# IR.net
KiCad netlist of a schematic drawn in EAGLE
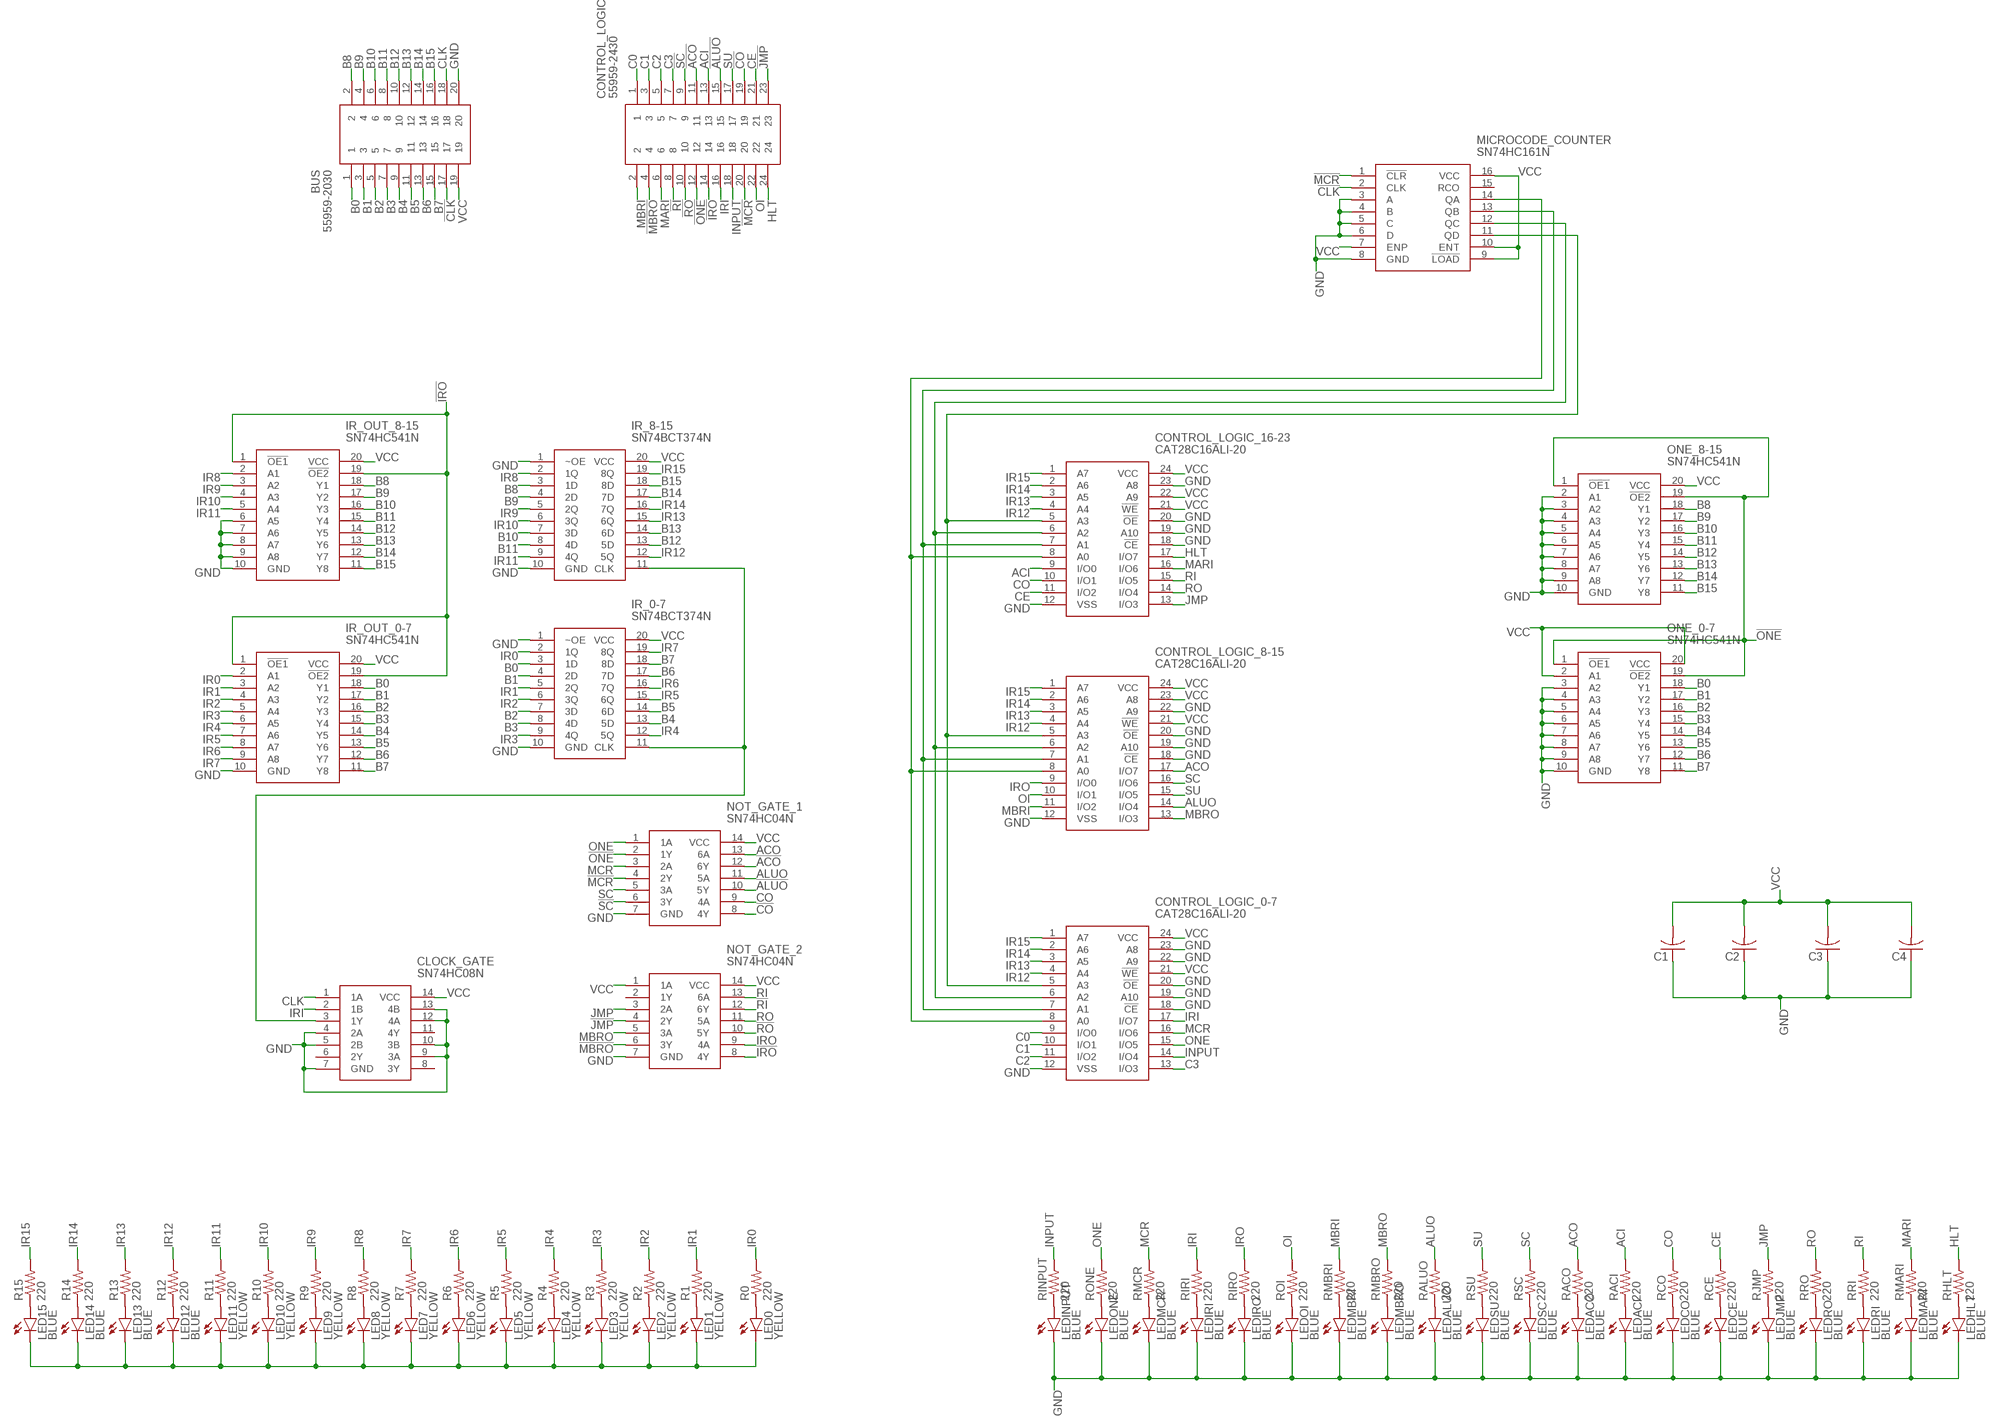
[diagram p0: schematic, sheet 1]

(export (version "E")
  (design (tool "Eeschema 10.0.6"))
  (components
    (comp (ref "BUS")
      (value "55959-2030")
      (footprint "eagle-import:55959-2030_1")
      (fields (field (name "MOUSER_PART_NUMBER") "538-55959-2030"))
      (libsource (lib "eagle-import") (part "55959-2030"))
    )
    (comp (ref "C1")
      (value "C-US025-024X044")
      (footprint "eagle-import:C025-024X044")
      (libsource (lib "eagle-import") (part "C-US025-024X044"))
    )
    (comp (ref "C2")
      (value "C-US025-024X044")
      (footprint "eagle-import:C025-024X044")
      (libsource (lib "eagle-import") (part "C-US025-024X044"))
    )
    (comp (ref "C3")
      (value "C-US025-024X044")
      (footprint "eagle-import:C025-024X044")
      (libsource (lib "eagle-import") (part "C-US025-024X044"))
    )
    (comp (ref "C4")
      (value "C-US025-024X044")
      (footprint "eagle-import:C025-024X044")
      (libsource (lib "eagle-import") (part "C-US025-024X044"))
    )
    (comp (ref "CLOCK_GATE")
      (value "SN74HC08N")
      (footprint "eagle-import:DIP794W53P254L1930H508Q14N")
      (fields (field (name "MOUSER_PART_NUMBER") "595-SN74HC08N"))
      (libsource (lib "eagle-import") (part "SN74HC08N"))
    )
    (comp (ref "CONTROL_LOGIC")
      (value "55959-2430")
      (footprint "eagle-import:559592430")
      (fields (field (name "MOUSER_PART_NUMBER") "538-55959-2430"))
      (libsource (lib "eagle-import") (part "55959-2430"))
    )
    (comp (ref "CONTROL_LOGIC_0-7")
      (value "CAT28C16ALI-20")
      (footprint "eagle-import:DIP1651W55P254L3188H635Q24N")
      (libsource (lib "eagle-import") (part "CAT28C16ALI-20"))
    )
    (comp (ref "CONTROL_LOGIC_8-15")
      (value "CAT28C16ALI-20")
      (footprint "eagle-import:DIP1651W55P254L3188H635Q24N")
      (libsource (lib "eagle-import") (part "CAT28C16ALI-20"))
    )
    (comp (ref "CONTROL_LOGIC_16-23")
      (value "CAT28C16ALI-20")
      (footprint "eagle-import:DIP1651W55P254L3188H635Q24N")
      (libsource (lib "eagle-import") (part "CAT28C16ALI-20"))
    )
    (comp (ref "IR_0-7")
      (value "SN74BCT374N")
      (footprint "eagle-import:DIP254P762X508-20")
      (fields (field (name "MOUSER_PART_NUMBER") "595-SN74BCT374N"))
      (libsource (lib "eagle-import") (part "SN74BCT374N"))
    )
    (comp (ref "IR_8-15")
      (value "SN74BCT374N")
      (footprint "eagle-import:DIP254P762X508-20")
      (fields (field (name "MOUSER_PART_NUMBER") "595-SN74BCT374N"))
      (libsource (lib "eagle-import") (part "SN74BCT374N"))
    )
    (comp (ref "IR_OUT_0-7")
      (value "SN74HC541N")
      (footprint "eagle-import:DIP794W53P254L2540H508Q20N")
      (fields (field (name "MOUSER_PART_NUMBER") "595-SN74HC541N"))
      (libsource (lib "eagle-import") (part "SN74HC541N"))
    )
    (comp (ref "IR_OUT_8-15")
      (value "SN74HC541N")
      (footprint "eagle-import:DIP794W53P254L2540H508Q20N")
      (fields (field (name "MOUSER_PART_NUMBER") "595-SN74HC541N"))
      (libsource (lib "eagle-import") (part "SN74HC541N"))
    )
    (comp (ref "LED0")
      (value "YELLOW")
      (footprint "eagle-import:LED3MM")
      (libsource (lib "eagle-import") (part "LED3MM"))
    )
    (comp (ref "LED1")
      (value "YELLOW")
      (footprint "eagle-import:LED3MM")
      (libsource (lib "eagle-import") (part "LED3MM"))
    )
    (comp (ref "LED2")
      (value "YELLOW")
      (footprint "eagle-import:LED3MM")
      (libsource (lib "eagle-import") (part "LED3MM"))
    )
    (comp (ref "LED3")
      (value "YELLOW")
      (footprint "eagle-import:LED3MM")
      (libsource (lib "eagle-import") (part "LED3MM"))
    )
    (comp (ref "LED4")
      (value "YELLOW")
      (footprint "eagle-import:LED3MM")
      (libsource (lib "eagle-import") (part "LED3MM"))
    )
    (comp (ref "LED5")
      (value "YELLOW")
      (footprint "eagle-import:LED3MM")
      (libsource (lib "eagle-import") (part "LED3MM"))
    )
    (comp (ref "LED6")
      (value "YELLOW")
      (footprint "eagle-import:LED3MM")
      (libsource (lib "eagle-import") (part "LED3MM"))
    )
    (comp (ref "LED7")
      (value "YELLOW")
      (footprint "eagle-import:LED3MM")
      (libsource (lib "eagle-import") (part "LED3MM"))
    )
    (comp (ref "LED8")
      (value "YELLOW")
      (footprint "eagle-import:LED3MM")
      (libsource (lib "eagle-import") (part "LED3MM"))
    )
    (comp (ref "LED9")
      (value "YELLOW")
      (footprint "eagle-import:LED3MM")
      (libsource (lib "eagle-import") (part "LED3MM"))
    )
    (comp (ref "LED10")
      (value "YELLOW")
      (footprint "eagle-import:LED3MM")
      (libsource (lib "eagle-import") (part "LED3MM"))
    )
    (comp (ref "LED11")
      (value "YELLOW")
      (footprint "eagle-import:LED3MM")
      (libsource (lib "eagle-import") (part "LED3MM"))
    )
    (comp (ref "LED12")
      (value "BLUE")
      (footprint "eagle-import:LED3MM")
      (libsource (lib "eagle-import") (part "LED3MM"))
    )
    (comp (ref "LED13")
      (value "BLUE")
      (footprint "eagle-import:LED3MM")
      (libsource (lib "eagle-import") (part "LED3MM"))
    )
    (comp (ref "LED14")
      (value "BLUE")
      (footprint "eagle-import:LED3MM")
      (libsource (lib "eagle-import") (part "LED3MM"))
    )
    (comp (ref "LED15")
      (value "BLUE")
      (footprint "eagle-import:LED3MM")
      (libsource (lib "eagle-import") (part "LED3MM"))
    )
    (comp (ref "LEDACI")
      (value "BLUE")
      (footprint "eagle-import:LED3MM")
      (libsource (lib "eagle-import") (part "LED3MM"))
    )
    (comp (ref "LEDACO")
      (value "BLUE")
      (footprint "eagle-import:LED3MM")
      (libsource (lib "eagle-import") (part "LED3MM"))
    )
    (comp (ref "LEDALUO")
      (value "BLUE")
      (footprint "eagle-import:LED3MM")
      (libsource (lib "eagle-import") (part "LED3MM"))
    )
    (comp (ref "LEDCE")
      (value "BLUE")
      (footprint "eagle-import:LED3MM")
      (libsource (lib "eagle-import") (part "LED3MM"))
    )
    (comp (ref "LEDCO")
      (value "BLUE")
      (footprint "eagle-import:LED3MM")
      (libsource (lib "eagle-import") (part "LED3MM"))
    )
    (comp (ref "LEDHLT")
      (value "BLUE")
      (footprint "eagle-import:LED3MM")
      (libsource (lib "eagle-import") (part "LED3MM"))
    )
    (comp (ref "LEDINPUT")
      (value "BLUE")
      (footprint "eagle-import:LED3MM")
      (libsource (lib "eagle-import") (part "LED3MM"))
    )
    (comp (ref "LEDIRI")
      (value "BLUE")
      (footprint "eagle-import:LED3MM")
      (libsource (lib "eagle-import") (part "LED3MM"))
    )
    (comp (ref "LEDIRO")
      (value "BLUE")
      (footprint "eagle-import:LED3MM")
      (libsource (lib "eagle-import") (part "LED3MM"))
    )
    (comp (ref "LEDJMP")
      (value "BLUE")
      (footprint "eagle-import:LED3MM")
      (libsource (lib "eagle-import") (part "LED3MM"))
    )
    (comp (ref "LEDMARI")
      (value "BLUE")
      (footprint "eagle-import:LED3MM")
      (libsource (lib "eagle-import") (part "LED3MM"))
    )
    (comp (ref "LEDMBRI")
      (value "BLUE")
      (footprint "eagle-import:LED3MM")
      (libsource (lib "eagle-import") (part "LED3MM"))
    )
    (comp (ref "LEDMBRO")
      (value "BLUE")
      (footprint "eagle-import:LED3MM")
      (libsource (lib "eagle-import") (part "LED3MM"))
    )
    (comp (ref "LEDMCR")
      (value "BLUE")
      (footprint "eagle-import:LED3MM")
      (libsource (lib "eagle-import") (part "LED3MM"))
    )
    (comp (ref "LEDOI")
      (value "BLUE")
      (footprint "eagle-import:LED3MM")
      (libsource (lib "eagle-import") (part "LED3MM"))
    )
    (comp (ref "LEDONE")
      (value "BLUE")
      (footprint "eagle-import:LED3MM")
      (libsource (lib "eagle-import") (part "LED3MM"))
    )
    (comp (ref "LEDRI")
      (value "BLUE")
      (footprint "eagle-import:LED3MM")
      (libsource (lib "eagle-import") (part "LED3MM"))
    )
    (comp (ref "LEDRO")
      (value "BLUE")
      (footprint "eagle-import:LED3MM")
      (libsource (lib "eagle-import") (part "LED3MM"))
    )
    (comp (ref "LEDSC")
      (value "BLUE")
      (footprint "eagle-import:LED3MM")
      (libsource (lib "eagle-import") (part "LED3MM"))
    )
    (comp (ref "LEDSU")
      (value "BLUE")
      (footprint "eagle-import:LED3MM")
      (libsource (lib "eagle-import") (part "LED3MM"))
    )
    (comp (ref "MICROCODE_COUNTER")
      (value "SN74HC161N")
      (footprint "eagle-import:DIP794W53P254L1930H508Q16N")
      (fields (field (name "MOUSER_PART_NUMBER") "595-SN74HC161N"))
      (libsource (lib "eagle-import") (part "SN74HC161N"))
    )
    (comp (ref "NOT_GATE_1")
      (value "SN74HC04N")
      (footprint "eagle-import:DIP794W53P254L1930H508Q14N")
      (fields (field (name "MOUSER_PART_NUMBER") "595-SN74HC04N"))
      (libsource (lib "eagle-import") (part "SN74HC04N"))
    )
    (comp (ref "NOT_GATE_2")
      (value "SN74HC04N")
      (footprint "eagle-import:DIP794W53P254L1930H508Q14N")
      (fields (field (name "MOUSER_PART_NUMBER") "595-SN74HC04N"))
      (libsource (lib "eagle-import") (part "SN74HC04N"))
    )
    (comp (ref "ONE_0-7")
      (value "SN74HC541N")
      (footprint "eagle-import:DIP794W53P254L2540H508Q20N")
      (fields (field (name "MOUSER_PART_NUMBER") "595-SN74HC541N"))
      (libsource (lib "eagle-import") (part "SN74HC541N"))
    )
    (comp (ref "ONE_8-15")
      (value "SN74HC541N")
      (footprint "eagle-import:DIP794W53P254L2540H508Q20N")
      (fields (field (name "MOUSER_PART_NUMBER") "595-SN74HC541N"))
      (libsource (lib "eagle-import") (part "SN74HC541N"))
    )
    (comp (ref "R0")
      (value "220")
      (footprint "eagle-import:0204_7")
      (libsource (lib "eagle-import") (part "R-US_0204/7"))
    )
    (comp (ref "R1")
      (value "220")
      (footprint "eagle-import:0204_7")
      (libsource (lib "eagle-import") (part "R-US_0204/7"))
    )
    (comp (ref "R2")
      (value "220")
      (footprint "eagle-import:0204_7")
      (libsource (lib "eagle-import") (part "R-US_0204/7"))
    )
    (comp (ref "R3")
      (value "220")
      (footprint "eagle-import:0204_7")
      (libsource (lib "eagle-import") (part "R-US_0204/7"))
    )
    (comp (ref "R4")
      (value "220")
      (footprint "eagle-import:0204_7")
      (libsource (lib "eagle-import") (part "R-US_0204/7"))
    )
    (comp (ref "R5")
      (value "220")
      (footprint "eagle-import:0204_7")
      (libsource (lib "eagle-import") (part "R-US_0204/7"))
    )
    (comp (ref "R6")
      (value "220")
      (footprint "eagle-import:0204_7")
      (libsource (lib "eagle-import") (part "R-US_0204/7"))
    )
    (comp (ref "R7")
      (value "220")
      (footprint "eagle-import:0204_7")
      (libsource (lib "eagle-import") (part "R-US_0204/7"))
    )
    (comp (ref "R8")
      (value "220")
      (footprint "eagle-import:0204_7")
      (libsource (lib "eagle-import") (part "R-US_0204/7"))
    )
    (comp (ref "R9")
      (value "220")
      (footprint "eagle-import:0204_7")
      (libsource (lib "eagle-import") (part "R-US_0204/7"))
    )
    (comp (ref "R10")
      (value "220")
      (footprint "eagle-import:0204_7")
      (libsource (lib "eagle-import") (part "R-US_0204/7"))
    )
    (comp (ref "R11")
      (value "220")
      (footprint "eagle-import:0204_7")
      (libsource (lib "eagle-import") (part "R-US_0204/7"))
    )
    (comp (ref "R12")
      (value "220")
      (footprint "eagle-import:0204_7")
      (libsource (lib "eagle-import") (part "R-US_0204/7"))
    )
    (comp (ref "R13")
      (value "220")
      (footprint "eagle-import:0204_7")
      (libsource (lib "eagle-import") (part "R-US_0204/7"))
    )
    (comp (ref "R14")
      (value "220")
      (footprint "eagle-import:0204_7")
      (libsource (lib "eagle-import") (part "R-US_0204/7"))
    )
    (comp (ref "R15")
      (value "220")
      (footprint "eagle-import:0204_7")
      (libsource (lib "eagle-import") (part "R-US_0204/7"))
    )
    (comp (ref "RACI")
      (value "220")
      (footprint "eagle-import:0204_7")
      (libsource (lib "eagle-import") (part "R-US_0204/7"))
    )
    (comp (ref "RACO")
      (value "220")
      (footprint "eagle-import:0204_7")
      (libsource (lib "eagle-import") (part "R-US_0204/7"))
    )
    (comp (ref "RALUO")
      (value "220")
      (footprint "eagle-import:0204_7")
      (libsource (lib "eagle-import") (part "R-US_0204/7"))
    )
    (comp (ref "RCE")
      (value "220")
      (footprint "eagle-import:0204_7")
      (libsource (lib "eagle-import") (part "R-US_0204/7"))
    )
    (comp (ref "RCO")
      (value "220")
      (footprint "eagle-import:0204_7")
      (libsource (lib "eagle-import") (part "R-US_0204/7"))
    )
    (comp (ref "RHLT")
      (value "220")
      (footprint "eagle-import:0204_7")
      (libsource (lib "eagle-import") (part "R-US_0204/7"))
    )
    (comp (ref "RINPUT")
      (value "220")
      (footprint "eagle-import:0204_7")
      (libsource (lib "eagle-import") (part "R-US_0204/7"))
    )
    (comp (ref "RIRI")
      (value "220")
      (footprint "eagle-import:0204_7")
      (libsource (lib "eagle-import") (part "R-US_0204/7"))
    )
    (comp (ref "RIRO")
      (value "220")
      (footprint "eagle-import:0204_7")
      (libsource (lib "eagle-import") (part "R-US_0204/7"))
    )
    (comp (ref "RJMP")
      (value "220")
      (footprint "eagle-import:0204_7")
      (libsource (lib "eagle-import") (part "R-US_0204/7"))
    )
    (comp (ref "RMARI")
      (value "220")
      (footprint "eagle-import:0204_7")
      (libsource (lib "eagle-import") (part "R-US_0204/7"))
    )
    (comp (ref "RMBRI")
      (value "220")
      (footprint "eagle-import:0204_7")
      (libsource (lib "eagle-import") (part "R-US_0204/7"))
    )
    (comp (ref "RMBRO")
      (value "220")
      (footprint "eagle-import:0204_7")
      (libsource (lib "eagle-import") (part "R-US_0204/7"))
    )
    (comp (ref "RMCR")
      (value "220")
      (footprint "eagle-import:0204_7")
      (libsource (lib "eagle-import") (part "R-US_0204/7"))
    )
    (comp (ref "ROI")
      (value "220")
      (footprint "eagle-import:0204_7")
      (libsource (lib "eagle-import") (part "R-US_0204/7"))
    )
    (comp (ref "RONE")
      (value "220")
      (footprint "eagle-import:0204_7")
      (libsource (lib "eagle-import") (part "R-US_0204/7"))
    )
    (comp (ref "RRI")
      (value "220")
      (footprint "eagle-import:0204_7")
      (libsource (lib "eagle-import") (part "R-US_0204/7"))
    )
    (comp (ref "RRO")
      (value "220")
      (footprint "eagle-import:0204_7")
      (libsource (lib "eagle-import") (part "R-US_0204/7"))
    )
    (comp (ref "RSC")
      (value "220")
      (footprint "eagle-import:0204_7")
      (libsource (lib "eagle-import") (part "R-US_0204/7"))
    )
    (comp (ref "RSU")
      (value "220")
      (footprint "eagle-import:0204_7")
      (libsource (lib "eagle-import") (part "R-US_0204/7"))
    )
  )
  (nets
    (net (code "1") (name "/ACI") (class "Default")
      (node (ref "CONTROL_LOGIC") (pin "13") (pinfunction "13_13") (pintype "bidirectional"))
      (node (ref "CONTROL_LOGIC_16-23") (pin "9") (pinfunction "I/O0_9") (pintype "bidirectional"))
      (node (ref "RACI") (pin "2") (pinfunction "2_2") (pintype "passive"))
    )
    (net (code "2") (name "/ACO") (class "Default")
      (node (ref "CONTROL_LOGIC_8-15") (pin "17") (pinfunction "I/O7_17") (pintype "bidirectional"))
      (node (ref "NOT_GATE_1") (pin "13") (pinfunction "6A_13") (pintype "bidirectional"))
      (node (ref "RACO") (pin "2") (pinfunction "2_2") (pintype "passive"))
    )
    (net (code "3") (name "/ALUO") (class "Default")
      (node (ref "CONTROL_LOGIC_8-15") (pin "14") (pinfunction "I/O4_14") (pintype "bidirectional"))
      (node (ref "NOT_GATE_1") (pin "11") (pinfunction "5A_11") (pintype "bidirectional"))
      (node (ref "RALUO") (pin "2") (pinfunction "2_2") (pintype "passive"))
    )
    (net (code "4") (name "/B0") (class "Default")
      (node (ref "BUS") (pin "1") (pinfunction "1_1") (pintype "bidirectional"))
      (node (ref "IR_0-7") (pin "3") (pinfunction "1D_3") (pintype "bidirectional"))
      (node (ref "IR_OUT_0-7") (pin "18") (pinfunction "Y1_18") (pintype "bidirectional"))
      (node (ref "ONE_0-7") (pin "18") (pinfunction "Y1_18") (pintype "bidirectional"))
    )
    (net (code "5") (name "/B1") (class "Default")
      (node (ref "BUS") (pin "3") (pinfunction "3_3") (pintype "bidirectional"))
      (node (ref "IR_0-7") (pin "4") (pinfunction "2D_4") (pintype "bidirectional"))
      (node (ref "IR_OUT_0-7") (pin "17") (pinfunction "Y2_17") (pintype "bidirectional"))
      (node (ref "ONE_0-7") (pin "17") (pinfunction "Y2_17") (pintype "bidirectional"))
    )
    (net (code "6") (name "/B2") (class "Default")
      (node (ref "BUS") (pin "5") (pinfunction "5_5") (pintype "bidirectional"))
      (node (ref "IR_0-7") (pin "7") (pinfunction "3D_7") (pintype "bidirectional"))
      (node (ref "IR_OUT_0-7") (pin "16") (pinfunction "Y3_16") (pintype "bidirectional"))
      (node (ref "ONE_0-7") (pin "16") (pinfunction "Y3_16") (pintype "bidirectional"))
    )
    (net (code "7") (name "/B3") (class "Default")
      (node (ref "BUS") (pin "7") (pinfunction "7_7") (pintype "bidirectional"))
      (node (ref "IR_0-7") (pin "8") (pinfunction "4D_8") (pintype "bidirectional"))
      (node (ref "IR_OUT_0-7") (pin "15") (pinfunction "Y4_15") (pintype "bidirectional"))
      (node (ref "ONE_0-7") (pin "15") (pinfunction "Y4_15") (pintype "bidirectional"))
    )
    (net (code "8") (name "/B4") (class "Default")
      (node (ref "BUS") (pin "9") (pinfunction "9_9") (pintype "bidirectional"))
      (node (ref "IR_0-7") (pin "13") (pinfunction "5D_13") (pintype "bidirectional"))
      (node (ref "IR_OUT_0-7") (pin "14") (pinfunction "Y5_14") (pintype "bidirectional"))
      (node (ref "ONE_0-7") (pin "14") (pinfunction "Y5_14") (pintype "bidirectional"))
    )
    (net (code "9") (name "/B5") (class "Default")
      (node (ref "BUS") (pin "11") (pinfunction "11_11") (pintype "bidirectional"))
      (node (ref "IR_0-7") (pin "14") (pinfunction "6D_14") (pintype "bidirectional"))
      (node (ref "IR_OUT_0-7") (pin "13") (pinfunction "Y6_13") (pintype "bidirectional"))
      (node (ref "ONE_0-7") (pin "13") (pinfunction "Y6_13") (pintype "bidirectional"))
    )
    (net (code "10") (name "/B6") (class "Default")
      (node (ref "BUS") (pin "13") (pinfunction "13_13") (pintype "bidirectional"))
      (node (ref "IR_0-7") (pin "17") (pinfunction "7D_17") (pintype "bidirectional"))
      (node (ref "IR_OUT_0-7") (pin "12") (pinfunction "Y7_12") (pintype "bidirectional"))
      (node (ref "ONE_0-7") (pin "12") (pinfunction "Y7_12") (pintype "bidirectional"))
    )
    (net (code "11") (name "/B7") (class "Default")
      (node (ref "BUS") (pin "15") (pinfunction "15_15") (pintype "bidirectional"))
      (node (ref "IR_0-7") (pin "18") (pinfunction "8D_18") (pintype "bidirectional"))
      (node (ref "IR_OUT_0-7") (pin "11") (pinfunction "Y8_11") (pintype "bidirectional"))
      (node (ref "ONE_0-7") (pin "11") (pinfunction "Y8_11") (pintype "bidirectional"))
    )
    (net (code "12") (name "/B8") (class "Default")
      (node (ref "BUS") (pin "2") (pinfunction "2_2") (pintype "bidirectional"))
      (node (ref "IR_8-15") (pin "3") (pinfunction "1D_3") (pintype "bidirectional"))
      (node (ref "IR_OUT_8-15") (pin "18") (pinfunction "Y1_18") (pintype "bidirectional"))
      (node (ref "ONE_8-15") (pin "18") (pinfunction "Y1_18") (pintype "bidirectional"))
    )
    (net (code "13") (name "/B9") (class "Default")
      (node (ref "BUS") (pin "4") (pinfunction "4_4") (pintype "bidirectional"))
      (node (ref "IR_8-15") (pin "4") (pinfunction "2D_4") (pintype "bidirectional"))
      (node (ref "IR_OUT_8-15") (pin "17") (pinfunction "Y2_17") (pintype "bidirectional"))
      (node (ref "ONE_8-15") (pin "17") (pinfunction "Y2_17") (pintype "bidirectional"))
    )
    (net (code "14") (name "/B10") (class "Default")
      (node (ref "BUS") (pin "6") (pinfunction "6_6") (pintype "bidirectional"))
      (node (ref "IR_8-15") (pin "7") (pinfunction "3D_7") (pintype "bidirectional"))
      (node (ref "IR_OUT_8-15") (pin "16") (pinfunction "Y3_16") (pintype "bidirectional"))
      (node (ref "ONE_8-15") (pin "16") (pinfunction "Y3_16") (pintype "bidirectional"))
    )
    (net (code "15") (name "/B11") (class "Default")
      (node (ref "BUS") (pin "8") (pinfunction "8_8") (pintype "bidirectional"))
      (node (ref "IR_8-15") (pin "8") (pinfunction "4D_8") (pintype "bidirectional"))
      (node (ref "IR_OUT_8-15") (pin "15") (pinfunction "Y4_15") (pintype "bidirectional"))
      (node (ref "ONE_8-15") (pin "15") (pinfunction "Y4_15") (pintype "bidirectional"))
    )
    (net (code "16") (name "/B12") (class "Default")
      (node (ref "BUS") (pin "10") (pinfunction "10_10") (pintype "bidirectional"))
      (node (ref "IR_8-15") (pin "13") (pinfunction "5D_13") (pintype "bidirectional"))
      (node (ref "IR_OUT_8-15") (pin "14") (pinfunction "Y5_14") (pintype "bidirectional"))
      (node (ref "ONE_8-15") (pin "14") (pinfunction "Y5_14") (pintype "bidirectional"))
    )
    (net (code "17") (name "/B13") (class "Default")
      (node (ref "BUS") (pin "12") (pinfunction "12_12") (pintype "bidirectional"))
      (node (ref "IR_8-15") (pin "14") (pinfunction "6D_14") (pintype "bidirectional"))
      (node (ref "IR_OUT_8-15") (pin "13") (pinfunction "Y6_13") (pintype "bidirectional"))
      (node (ref "ONE_8-15") (pin "13") (pinfunction "Y6_13") (pintype "bidirectional"))
    )
    (net (code "18") (name "/B14") (class "Default")
      (node (ref "BUS") (pin "14") (pinfunction "14_14") (pintype "bidirectional"))
      (node (ref "IR_8-15") (pin "17") (pinfunction "7D_17") (pintype "bidirectional"))
      (node (ref "IR_OUT_8-15") (pin "12") (pinfunction "Y7_12") (pintype "bidirectional"))
      (node (ref "ONE_8-15") (pin "12") (pinfunction "Y7_12") (pintype "bidirectional"))
    )
    (net (code "19") (name "/B15") (class "Default")
      (node (ref "BUS") (pin "16") (pinfunction "16_16") (pintype "bidirectional"))
      (node (ref "IR_8-15") (pin "18") (pinfunction "8D_18") (pintype "bidirectional"))
      (node (ref "IR_OUT_8-15") (pin "11") (pinfunction "Y8_11") (pintype "bidirectional"))
      (node (ref "ONE_8-15") (pin "11") (pinfunction "Y8_11") (pintype "bidirectional"))
    )
    (net (code "20") (name "/C0") (class "Default")
      (node (ref "CONTROL_LOGIC") (pin "1") (pinfunction "1_1") (pintype "bidirectional"))
      (node (ref "CONTROL_LOGIC_0-7") (pin "9") (pinfunction "I/O0_9") (pintype "bidirectional"))
    )
    (net (code "21") (name "/C1") (class "Default")
      (node (ref "CONTROL_LOGIC") (pin "3") (pinfunction "3_3") (pintype "bidirectional"))
      (node (ref "CONTROL_LOGIC_0-7") (pin "10") (pinfunction "I/O1_10") (pintype "bidirectional"))
    )
    (net (code "22") (name "/C2") (class "Default")
      (node (ref "CONTROL_LOGIC") (pin "5") (pinfunction "5_5") (pintype "bidirectional"))
      (node (ref "CONTROL_LOGIC_0-7") (pin "11") (pinfunction "I/O2_11") (pintype "bidirectional"))
    )
    (net (code "23") (name "/C3") (class "Default")
      (node (ref "CONTROL_LOGIC") (pin "7") (pinfunction "7_7") (pintype "bidirectional"))
      (node (ref "CONTROL_LOGIC_0-7") (pin "13") (pinfunction "I/O3_13") (pintype "bidirectional"))
    )
    (net (code "24") (name "/CE") (class "Default")
      (node (ref "CONTROL_LOGIC") (pin "21") (pinfunction "21_21") (pintype "bidirectional"))
      (node (ref "CONTROL_LOGIC_16-23") (pin "11") (pinfunction "I/O2_11") (pintype "bidirectional"))
      (node (ref "RCE") (pin "2") (pinfunction "2_2") (pintype "passive"))
    )
    (net (code "25") (name "/CLK") (class "Default")
      (node (ref "BUS") (pin "18") (pinfunction "18_18") (pintype "bidirectional"))
      (node (ref "CLOCK_GATE") (pin "1") (pinfunction "1A_1") (pintype "bidirectional"))
    )
    (net (code "26") (name "/CO") (class "Default")
      (node (ref "CONTROL_LOGIC_16-23") (pin "10") (pinfunction "I/O1_10") (pintype "bidirectional"))
      (node (ref "NOT_GATE_1") (pin "9") (pinfunction "4A_9") (pintype "bidirectional"))
      (node (ref "RCO") (pin "2") (pinfunction "2_2") (pintype "passive"))
    )
    (net (code "27") (name "/GND") (class "Default")
      (node (ref "BUS") (pin "20") (pinfunction "20_20") (pintype "bidirectional"))
      (node (ref "C1") (pin "1") (pinfunction "1_1") (pintype "passive"))
      (node (ref "C2") (pin "1") (pinfunction "1_1") (pintype "passive"))
      (node (ref "C3") (pin "1") (pinfunction "1_1") (pintype "passive"))
      (node (ref "C4") (pin "1") (pinfunction "1_1") (pintype "passive"))
      (node (ref "CLOCK_GATE") (pin "10") (pinfunction "3B_10") (pintype "bidirectional"))
      (node (ref "CLOCK_GATE") (pin "12") (pinfunction "4A_12") (pintype "bidirectional"))
      (node (ref "CLOCK_GATE") (pin "13") (pinfunction "4B_13") (pintype "bidirectional"))
      (node (ref "CLOCK_GATE") (pin "4") (pinfunction "2A_4") (pintype "bidirectional"))
      (node (ref "CLOCK_GATE") (pin "5") (pinfunction "2B_5") (pintype "bidirectional"))
      (node (ref "CLOCK_GATE") (pin "7") (pinfunction "GND_7") (pintype "bidirectional"))
      (node (ref "CLOCK_GATE") (pin "9") (pinfunction "3A_9") (pintype "bidirectional"))
      (node (ref "CONTROL_LOGIC_0-7") (pin "12") (pinfunction "VSS_12") (pintype "bidirectional"))
      (node (ref "CONTROL_LOGIC_0-7") (pin "18") (pinfunction "~{CE}_18") (pintype "bidirectional"))
      (node (ref "CONTROL_LOGIC_0-7") (pin "19") (pinfunction "A10_19") (pintype "bidirectional"))
      (node (ref "CONTROL_LOGIC_0-7") (pin "20") (pinfunction "~{OE}_20") (pintype "bidirectional"))
      (node (ref "CONTROL_LOGIC_0-7") (pin "22") (pinfunction "A9_22") (pintype "bidirectional"))
      (node (ref "CONTROL_LOGIC_0-7") (pin "23") (pinfunction "A8_23") (pintype "bidirectional"))
      (node (ref "CONTROL_LOGIC_16-23") (pin "12") (pinfunction "VSS_12") (pintype "bidirectional"))
      (node (ref "CONTROL_LOGIC_16-23") (pin "18") (pinfunction "~{CE}_18") (pintype "bidirectional"))
      (node (ref "CONTROL_LOGIC_16-23") (pin "19") (pinfunction "A10_19") (pintype "bidirectional"))
      (node (ref "CONTROL_LOGIC_16-23") (pin "20") (pinfunction "~{OE}_20") (pintype "bidirectional"))
      (node (ref "CONTROL_LOGIC_16-23") (pin "23") (pinfunction "A8_23") (pintype "bidirectional"))
      (node (ref "CONTROL_LOGIC_8-15") (pin "12") (pinfunction "VSS_12") (pintype "bidirectional"))
      (node (ref "CONTROL_LOGIC_8-15") (pin "18") (pinfunction "~{CE}_18") (pintype "bidirectional"))
      (node (ref "CONTROL_LOGIC_8-15") (pin "19") (pinfunction "A10_19") (pintype "bidirectional"))
      (node (ref "CONTROL_LOGIC_8-15") (pin "20") (pinfunction "~{OE}_20") (pintype "bidirectional"))
      (node (ref "CONTROL_LOGIC_8-15") (pin "22") (pinfunction "A9_22") (pintype "bidirectional"))
      (node (ref "IR_0-7") (pin "1") (pinfunction "~{OE}_1") (pintype "bidirectional"))
      (node (ref "IR_0-7") (pin "10") (pinfunction "GND_10") (pintype "bidirectional"))
      (node (ref "IR_8-15") (pin "1") (pinfunction "~{OE}_1") (pintype "bidirectional"))
      (node (ref "IR_8-15") (pin "10") (pinfunction "GND_10") (pintype "bidirectional"))
      (node (ref "IR_OUT_0-7") (pin "10") (pinfunction "GND_10") (pintype "bidirectional"))
      (node (ref "IR_OUT_8-15") (pin "10") (pinfunction "GND_10") (pintype "bidirectional"))
      (node (ref "IR_OUT_8-15") (pin "6") (pinfunction "A5_6") (pintype "bidirectional"))
      (node (ref "IR_OUT_8-15") (pin "7") (pinfunction "A6_7") (pintype "bidirectional"))
      (node (ref "IR_OUT_8-15") (pin "8") (pinfunction "A7_8") (pintype "bidirectional"))
      (node (ref "IR_OUT_8-15") (pin "9") (pinfunction "A8_9") (pintype "bidirectional"))
      (node (ref "LEDACI") (pin "K") (pinfunction "C_K") (pintype "passive"))
      (node (ref "LEDACO") (pin "K") (pinfunction "C_K") (pintype "passive"))
      (node (ref "LEDALUO") (pin "K") (pinfunction "C_K") (pintype "passive"))
      (node (ref "LEDCE") (pin "K") (pinfunction "C_K") (pintype "passive"))
      (node (ref "LEDCO") (pin "K") (pinfunction "C_K") (pintype "passive"))
      (node (ref "LEDHLT") (pin "K") (pinfunction "C_K") (pintype "passive"))
      (node (ref "LEDINPUT") (pin "K") (pinfunction "C_K") (pintype "passive"))
      (node (ref "LEDIRI") (pin "K") (pinfunction "C_K") (pintype "passive"))
      (node (ref "LEDIRO") (pin "K") (pinfunction "C_K") (pintype "passive"))
      (node (ref "LEDJMP") (pin "K") (pinfunction "C_K") (pintype "passive"))
      (node (ref "LEDMARI") (pin "K") (pinfunction "C_K") (pintype "passive"))
      (node (ref "LEDMBRI") (pin "K") (pinfunction "C_K") (pintype "passive"))
      (node (ref "LEDMBRO") (pin "K") (pinfunction "C_K") (pintype "passive"))
      (node (ref "LEDMCR") (pin "K") (pinfunction "C_K") (pintype "passive"))
      (node (ref "LEDOI") (pin "K") (pinfunction "C_K") (pintype "passive"))
      (node (ref "LEDONE") (pin "K") (pinfunction "C_K") (pintype "passive"))
      (node (ref "LEDRI") (pin "K") (pinfunction "C_K") (pintype "passive"))
      (node (ref "LEDRO") (pin "K") (pinfunction "C_K") (pintype "passive"))
      (node (ref "LEDSC") (pin "K") (pinfunction "C_K") (pintype "passive"))
      (node (ref "LEDSU") (pin "K") (pinfunction "C_K") (pintype "passive"))
      (node (ref "MICROCODE_COUNTER") (pin "3") (pinfunction "A_3") (pintype "bidirectional"))
      (node (ref "MICROCODE_COUNTER") (pin "4") (pinfunction "B_4") (pintype "bidirectional"))
      (node (ref "MICROCODE_COUNTER") (pin "5") (pinfunction "C_5") (pintype "bidirectional"))
      (node (ref "MICROCODE_COUNTER") (pin "6") (pinfunction "D_6") (pintype "bidirectional"))
      (node (ref "MICROCODE_COUNTER") (pin "8") (pinfunction "GND_8") (pintype "bidirectional"))
      (node (ref "NOT_GATE_1") (pin "7") (pinfunction "GND_7") (pintype "bidirectional"))
      (node (ref "NOT_GATE_2") (pin "7") (pinfunction "GND_7") (pintype "bidirectional"))
      (node (ref "ONE_0-7") (pin "10") (pinfunction "GND_10") (pintype "bidirectional"))
      (node (ref "ONE_0-7") (pin "3") (pinfunction "A2_3") (pintype "bidirectional"))
      (node (ref "ONE_0-7") (pin "4") (pinfunction "A3_4") (pintype "bidirectional"))
      (node (ref "ONE_0-7") (pin "5") (pinfunction "A4_5") (pintype "bidirectional"))
      (node (ref "ONE_0-7") (pin "6") (pinfunction "A5_6") (pintype "bidirectional"))
      (node (ref "ONE_0-7") (pin "7") (pinfunction "A6_7") (pintype "bidirectional"))
      (node (ref "ONE_0-7") (pin "8") (pinfunction "A7_8") (pintype "bidirectional"))
      (node (ref "ONE_0-7") (pin "9") (pinfunction "A8_9") (pintype "bidirectional"))
      (node (ref "ONE_8-15") (pin "10") (pinfunction "GND_10") (pintype "bidirectional"))
      (node (ref "ONE_8-15") (pin "2") (pinfunction "A1_2") (pintype "bidirectional"))
      (node (ref "ONE_8-15") (pin "3") (pinfunction "A2_3") (pintype "bidirectional"))
      (node (ref "ONE_8-15") (pin "4") (pinfunction "A3_4") (pintype "bidirectional"))
      (node (ref "ONE_8-15") (pin "5") (pinfunction "A4_5") (pintype "bidirectional"))
      (node (ref "ONE_8-15") (pin "6") (pinfunction "A5_6") (pintype "bidirectional"))
      (node (ref "ONE_8-15") (pin "7") (pinfunction "A6_7") (pintype "bidirectional"))
      (node (ref "ONE_8-15") (pin "8") (pinfunction "A7_8") (pintype "bidirectional"))
      (node (ref "ONE_8-15") (pin "9") (pinfunction "A8_9") (pintype "bidirectional"))
    )
    (net (code "28") (name "/HLT") (class "Default")
      (node (ref "CONTROL_LOGIC") (pin "24") (pinfunction "24_24") (pintype "bidirectional"))
      (node (ref "CONTROL_LOGIC_16-23") (pin "17") (pinfunction "I/O7_17") (pintype "bidirectional"))
      (node (ref "RHLT") (pin "2") (pinfunction "2_2") (pintype "passive"))
    )
    (net (code "29") (name "/INPUT") (class "Default")
      (node (ref "CONTROL_LOGIC") (pin "18") (pinfunction "18_18") (pintype "bidirectional"))
      (node (ref "CONTROL_LOGIC_0-7") (pin "14") (pinfunction "I/O4_14") (pintype "bidirectional"))
      (node (ref "RINPUT") (pin "2") (pinfunction "2_2") (pintype "passive"))
    )
    (net (code "30") (name "/IR0") (class "Default")
      (node (ref "IR_0-7") (pin "2") (pinfunction "1Q_2") (pintype "bidirectional"))
      (node (ref "IR_OUT_0-7") (pin "2") (pinfunction "A1_2") (pintype "bidirectional"))
      (node (ref "R0") (pin "2") (pinfunction "2_2") (pintype "passive"))
    )
    (net (code "31") (name "/IR1") (class "Default")
      (node (ref "IR_0-7") (pin "5") (pinfunction "2Q_5") (pintype "bidirectional"))
      (node (ref "IR_OUT_0-7") (pin "3") (pinfunction "A2_3") (pintype "bidirectional"))
      (node (ref "R1") (pin "2") (pinfunction "2_2") (pintype "passive"))
    )
    (net (code "32") (name "/IR2") (class "Default")
      (node (ref "IR_0-7") (pin "6") (pinfunction "3Q_6") (pintype "bidirectional"))
      (node (ref "IR_OUT_0-7") (pin "4") (pinfunction "A3_4") (pintype "bidirectional"))
      (node (ref "R2") (pin "2") (pinfunction "2_2") (pintype "passive"))
    )
    (net (code "33") (name "/IR3") (class "Default")
      (node (ref "IR_0-7") (pin "9") (pinfunction "4Q_9") (pintype "bidirectional"))
      (node (ref "IR_OUT_0-7") (pin "5") (pinfunction "A4_5") (pintype "bidirectional"))
      (node (ref "R3") (pin "2") (pinfunction "2_2") (pintype "passive"))
    )
    (net (code "34") (name "/IR4") (class "Default")
      (node (ref "IR_0-7") (pin "12") (pinfunction "5Q_12") (pintype "bidirectional"))
      (node (ref "IR_OUT_0-7") (pin "6") (pinfunction "A5_6") (pintype "bidirectional"))
      (node (ref "R4") (pin "2") (pinfunction "2_2") (pintype "passive"))
    )
    (net (code "35") (name "/IR5") (class "Default")
      (node (ref "IR_0-7") (pin "15") (pinfunction "6Q_15") (pintype "bidirectional"))
      (node (ref "IR_OUT_0-7") (pin "7") (pinfunction "A6_7") (pintype "bidirectional"))
      (node (ref "R5") (pin "2") (pinfunction "2_2") (pintype "passive"))
    )
    (net (code "36") (name "/IR6") (class "Default")
      (node (ref "IR_0-7") (pin "16") (pinfunction "7Q_16") (pintype "bidirectional"))
      (node (ref "IR_OUT_0-7") (pin "8") (pinfunction "A7_8") (pintype "bidirectional"))
      (node (ref "R6") (pin "2") (pinfunction "2_2") (pintype "passive"))
    )
    (net (code "37") (name "/IR7") (class "Default")
      (node (ref "IR_0-7") (pin "19") (pinfunction "8Q_19") (pintype "bidirectional"))
      (node (ref "IR_OUT_0-7") (pin "9") (pinfunction "A8_9") (pintype "bidirectional"))
      (node (ref "R7") (pin "2") (pinfunction "2_2") (pintype "passive"))
    )
    (net (code "38") (name "/IR8") (class "Default")
      (node (ref "IR_8-15") (pin "2") (pinfunction "1Q_2") (pintype "bidirectional"))
      (node (ref "IR_OUT_8-15") (pin "2") (pinfunction "A1_2") (pintype "bidirectional"))
      (node (ref "R8") (pin "2") (pinfunction "2_2") (pintype "passive"))
    )
    (net (code "39") (name "/IR9") (class "Default")
      (node (ref "IR_8-15") (pin "5") (pinfunction "2Q_5") (pintype "bidirectional"))
      (node (ref "IR_OUT_8-15") (pin "3") (pinfunction "A2_3") (pintype "bidirectional"))
      (node (ref "R9") (pin "2") (pinfunction "2_2") (pintype "passive"))
    )
    (net (code "40") (name "/IR10") (class "Default")
      (node (ref "IR_8-15") (pin "6") (pinfunction "3Q_6") (pintype "bidirectional"))
      (node (ref "IR_OUT_8-15") (pin "4") (pinfunction "A3_4") (pintype "bidirectional"))
      (node (ref "R10") (pin "2") (pinfunction "2_2") (pintype "passive"))
    )
    (net (code "41") (name "/IR11") (class "Default")
      (node (ref "IR_8-15") (pin "9") (pinfunction "4Q_9") (pintype "bidirectional"))
      (node (ref "IR_OUT_8-15") (pin "5") (pinfunction "A4_5") (pintype "bidirectional"))
      (node (ref "R11") (pin "2") (pinfunction "2_2") (pintype "passive"))
    )
    (net (code "42") (name "/IR12") (class "Default")
      (node (ref "CONTROL_LOGIC_0-7") (pin "4") (pinfunction "A4_4") (pintype "bidirectional"))
      (node (ref "CONTROL_LOGIC_16-23") (pin "4") (pinfunction "A4_4") (pintype "bidirectional"))
      (node (ref "CONTROL_LOGIC_8-15") (pin "4") (pinfunction "A4_4") (pintype "bidirectional"))
      (node (ref "IR_8-15") (pin "12") (pinfunction "5Q_12") (pintype "bidirectional"))
      (node (ref "R12") (pin "2") (pinfunction "2_2") (pintype "passive"))
    )
    (net (code "43") (name "/IR13") (class "Default")
      (node (ref "CONTROL_LOGIC_0-7") (pin "3") (pinfunction "A5_3") (pintype "bidirectional"))
      (node (ref "CONTROL_LOGIC_16-23") (pin "3") (pinfunction "A5_3") (pintype "bidirectional"))
      (node (ref "CONTROL_LOGIC_8-15") (pin "3") (pinfunction "A5_3") (pintype "bidirectional"))
      (node (ref "IR_8-15") (pin "15") (pinfunction "6Q_15") (pintype "bidirectional"))
      (node (ref "R13") (pin "2") (pinfunction "2_2") (pintype "passive"))
    )
    (net (code "44") (name "/IR14") (class "Default")
      (node (ref "CONTROL_LOGIC_0-7") (pin "2") (pinfunction "A6_2") (pintype "bidirectional"))
      (node (ref "CONTROL_LOGIC_16-23") (pin "2") (pinfunction "A6_2") (pintype "bidirectional"))
      (node (ref "CONTROL_LOGIC_8-15") (pin "2") (pinfunction "A6_2") (pintype "bidirectional"))
      (node (ref "IR_8-15") (pin "16") (pinfunction "7Q_16") (pintype "bidirectional"))
      (node (ref "R14") (pin "2") (pinfunction "2_2") (pintype "passive"))
    )
    (net (code "45") (name "/IR15") (class "Default")
      (node (ref "CONTROL_LOGIC_0-7") (pin "1") (pinfunction "A7_1") (pintype "bidirectional"))
      (node (ref "CONTROL_LOGIC_16-23") (pin "1") (pinfunction "A7_1") (pintype "bidirectional"))
      (node (ref "CONTROL_LOGIC_8-15") (pin "1") (pinfunction "A7_1") (pintype "bidirectional"))
      (node (ref "IR_8-15") (pin "19") (pinfunction "8Q_19") (pintype "bidirectional"))
      (node (ref "R15") (pin "2") (pinfunction "2_2") (pintype "passive"))
    )
    (net (code "46") (name "/IRI") (class "Default")
      (node (ref "CLOCK_GATE") (pin "2") (pinfunction "1B_2") (pintype "bidirectional"))
      (node (ref "CONTROL_LOGIC") (pin "16") (pinfunction "16_16") (pintype "bidirectional"))
      (node (ref "CONTROL_LOGIC_0-7") (pin "17") (pinfunction "I/O7_17") (pintype "bidirectional"))
      (node (ref "RIRI") (pin "2") (pinfunction "2_2") (pintype "passive"))
    )
    (net (code "47") (name "/IRO") (class "Default")
      (node (ref "CONTROL_LOGIC_8-15") (pin "9") (pinfunction "I/O0_9") (pintype "bidirectional"))
      (node (ref "NOT_GATE_2") (pin "9") (pinfunction "4A_9") (pintype "bidirectional"))
      (node (ref "RIRO") (pin "2") (pinfunction "2_2") (pintype "passive"))
    )
    (net (code "48") (name "/JMP") (class "Default")
      (node (ref "CONTROL_LOGIC_16-23") (pin "13") (pinfunction "I/O3_13") (pintype "bidirectional"))
      (node (ref "NOT_GATE_2") (pin "3") (pinfunction "2A_3") (pintype "bidirectional"))
      (node (ref "RJMP") (pin "2") (pinfunction "2_2") (pintype "passive"))
    )
    (net (code "49") (name "/MARI") (class "Default")
      (node (ref "CONTROL_LOGIC") (pin "6") (pinfunction "6_6") (pintype "bidirectional"))
      (node (ref "CONTROL_LOGIC_16-23") (pin "16") (pinfunction "I/O6_16") (pintype "bidirectional"))
      (node (ref "RMARI") (pin "2") (pinfunction "2_2") (pintype "passive"))
    )
    (net (code "50") (name "/MBRI") (class "Default")
      (node (ref "CONTROL_LOGIC") (pin "2") (pinfunction "2_2") (pintype "bidirectional"))
      (node (ref "CONTROL_LOGIC_8-15") (pin "11") (pinfunction "I/O2_11") (pintype "bidirectional"))
      (node (ref "RMBRI") (pin "2") (pinfunction "2_2") (pintype "passive"))
    )
    (net (code "51") (name "/MBRO") (class "Default")
      (node (ref "CONTROL_LOGIC_8-15") (pin "13") (pinfunction "I/O3_13") (pintype "bidirectional"))
      (node (ref "NOT_GATE_2") (pin "5") (pinfunction "3A_5") (pintype "bidirectional"))
      (node (ref "RMBRO") (pin "2") (pinfunction "2_2") (pintype "passive"))
    )
    (net (code "52") (name "/MCR") (class "Default")
      (node (ref "CONTROL_LOGIC_0-7") (pin "16") (pinfunction "I/O6_16") (pintype "bidirectional"))
      (node (ref "NOT_GATE_1") (pin "3") (pinfunction "2A_3") (pintype "bidirectional"))
      (node (ref "RMCR") (pin "2") (pinfunction "2_2") (pintype "passive"))
    )
    (net (code "53") (name "/OI") (class "Default")
      (node (ref "CONTROL_LOGIC") (pin "22") (pinfunction "22_22") (pintype "bidirectional"))
      (node (ref "CONTROL_LOGIC_8-15") (pin "10") (pinfunction "I/O1_10") (pintype "bidirectional"))
      (node (ref "ROI") (pin "2") (pinfunction "2_2") (pintype "passive"))
    )
    (net (code "54") (name "/ONE") (class "Default")
      (node (ref "CONTROL_LOGIC_0-7") (pin "15") (pinfunction "I/O5_15") (pintype "bidirectional"))
      (node (ref "NOT_GATE_1") (pin "1") (pinfunction "1A_1") (pintype "bidirectional"))
      (node (ref "RONE") (pin "2") (pinfunction "2_2") (pintype "passive"))
    )
    (net (code "55") (name "/RI") (class "Default")
      (node (ref "CONTROL_LOGIC_16-23") (pin "15") (pinfunction "I/O5_15") (pintype "bidirectional"))
      (node (ref "NOT_GATE_2") (pin "13") (pinfunction "6A_13") (pintype "bidirectional"))
      (node (ref "RRI") (pin "2") (pinfunction "2_2") (pintype "passive"))
    )
    (net (code "56") (name "/RO") (class "Default")
      (node (ref "CONTROL_LOGIC_16-23") (pin "14") (pinfunction "I/O4_14") (pintype "bidirectional"))
      (node (ref "NOT_GATE_2") (pin "11") (pinfunction "5A_11") (pintype "bidirectional"))
      (node (ref "RRO") (pin "2") (pinfunction "2_2") (pintype "passive"))
    )
    (net (code "57") (name "/SC") (class "Default")
      (node (ref "CONTROL_LOGIC_8-15") (pin "16") (pinfunction "I/O6_16") (pintype "bidirectional"))
      (node (ref "NOT_GATE_1") (pin "5") (pinfunction "3A_5") (pintype "bidirectional"))
      (node (ref "RSC") (pin "2") (pinfunction "2_2") (pintype "passive"))
    )
    (net (code "58") (name "/SU") (class "Default")
      (node (ref "CONTROL_LOGIC") (pin "17") (pinfunction "17_17") (pintype "bidirectional"))
      (node (ref "CONTROL_LOGIC_8-15") (pin "15") (pinfunction "I/O5_15") (pintype "bidirectional"))
      (node (ref "RSU") (pin "2") (pinfunction "2_2") (pintype "passive"))
    )
    (net (code "59") (name "/VCC") (class "Default")
      (node (ref "BUS") (pin "19") (pinfunction "19_19") (pintype "bidirectional"))
      (node (ref "C1") (pin "2") (pinfunction "2_2") (pintype "passive"))
      (node (ref "C2") (pin "2") (pinfunction "2_2") (pintype "passive"))
      (node (ref "C3") (pin "2") (pinfunction "2_2") (pintype "passive"))
      (node (ref "C4") (pin "2") (pinfunction "2_2") (pintype "passive"))
      (node (ref "CLOCK_GATE") (pin "14") (pinfunction "VCC_14") (pintype "bidirectional"))
      (node (ref "CONTROL_LOGIC_0-7") (pin "21") (pinfunction "~{WE}_21") (pintype "bidirectional"))
      (node (ref "CONTROL_LOGIC_0-7") (pin "24") (pinfunction "VCC_24") (pintype "bidirectional"))
      (node (ref "CONTROL_LOGIC_16-23") (pin "21") (pinfunction "~{WE}_21") (pintype "bidirectional"))
      (node (ref "CONTROL_LOGIC_16-23") (pin "22") (pinfunction "A9_22") (pintype "bidirectional"))
      (node (ref "CONTROL_LOGIC_16-23") (pin "24") (pinfunction "VCC_24") (pintype "bidirectional"))
      (node (ref "CONTROL_LOGIC_8-15") (pin "21") (pinfunction "~{WE}_21") (pintype "bidirectional"))
      (node (ref "CONTROL_LOGIC_8-15") (pin "23") (pinfunction "A8_23") (pintype "bidirectional"))
      (node (ref "CONTROL_LOGIC_8-15") (pin "24") (pinfunction "VCC_24") (pintype "bidirectional"))
      (node (ref "IR_0-7") (pin "20") (pinfunction "VCC_20") (pintype "bidirectional"))
      (node (ref "IR_8-15") (pin "20") (pinfunction "VCC_20") (pintype "bidirectional"))
      (node (ref "IR_OUT_0-7") (pin "20") (pinfunction "VCC_20") (pintype "bidirectional"))
      (node (ref "IR_OUT_8-15") (pin "20") (pinfunction "VCC_20") (pintype "bidirectional"))
      (node (ref "MICROCODE_COUNTER") (pin "10") (pinfunction "ENT_10") (pintype "bidirectional"))
      (node (ref "MICROCODE_COUNTER") (pin "16") (pinfunction "VCC_16") (pintype "bidirectional"))
      (node (ref "MICROCODE_COUNTER") (pin "7") (pinfunction "ENP_7") (pintype "bidirectional"))
      (node (ref "MICROCODE_COUNTER") (pin "9") (pinfunction "~{LOAD}_9") (pintype "bidirectional"))
      (node (ref "NOT_GATE_1") (pin "14") (pinfunction "VCC_14") (pintype "bidirectional"))
      (node (ref "NOT_GATE_2") (pin "1") (pinfunction "1A_1") (pintype "bidirectional"))
      (node (ref "NOT_GATE_2") (pin "14") (pinfunction "VCC_14") (pintype "bidirectional"))
      (node (ref "ONE_0-7") (pin "2") (pinfunction "A1_2") (pintype "bidirectional"))
      (node (ref "ONE_0-7") (pin "20") (pinfunction "VCC_20") (pintype "bidirectional"))
      (node (ref "ONE_8-15") (pin "20") (pinfunction "VCC_20") (pintype "bidirectional"))
    )
    (net (code "60") (name "/~{ACO}") (class "Default")
      (node (ref "CONTROL_LOGIC") (pin "11") (pinfunction "11_11") (pintype "bidirectional"))
      (node (ref "NOT_GATE_1") (pin "12") (pinfunction "6Y_12") (pintype "bidirectional"))
    )
    (net (code "61") (name "/~{ALUO}") (class "Default")
      (node (ref "CONTROL_LOGIC") (pin "15") (pinfunction "15_15") (pintype "bidirectional"))
      (node (ref "NOT_GATE_1") (pin "10") (pinfunction "5Y_10") (pintype "bidirectional"))
    )
    (net (code "62") (name "/~{CLK}") (class "Default")
      (node (ref "BUS") (pin "17") (pinfunction "17_17") (pintype "bidirectional"))
      (node (ref "MICROCODE_COUNTER") (pin "2") (pinfunction "CLK_2") (pintype "bidirectional"))
    )
    (net (code "63") (name "/~{CO}") (class "Default")
      (node (ref "CONTROL_LOGIC") (pin "19") (pinfunction "19_19") (pintype "bidirectional"))
      (node (ref "NOT_GATE_1") (pin "8") (pinfunction "4Y_8") (pintype "bidirectional"))
    )
    (net (code "64") (name "/~{IRO}") (class "Default")
      (node (ref "CONTROL_LOGIC") (pin "14") (pinfunction "14_14") (pintype "bidirectional"))
      (node (ref "IR_OUT_0-7") (pin "1") (pinfunction "~{OE1}_1") (pintype "bidirectional"))
      (node (ref "IR_OUT_0-7") (pin "19") (pinfunction "~{OE2}_19") (pintype "bidirectional"))
      (node (ref "IR_OUT_8-15") (pin "1") (pinfunction "~{OE1}_1") (pintype "bidirectional"))
      (node (ref "IR_OUT_8-15") (pin "19") (pinfunction "~{OE2}_19") (pintype "bidirectional"))
      (node (ref "NOT_GATE_2") (pin "8") (pinfunction "4Y_8") (pintype "bidirectional"))
    )
    (net (code "65") (name "/~{JMP}") (class "Default")
      (node (ref "CONTROL_LOGIC") (pin "23") (pinfunction "23_23") (pintype "bidirectional"))
      (node (ref "NOT_GATE_2") (pin "4") (pinfunction "2Y_4") (pintype "bidirectional"))
    )
    (net (code "66") (name "/~{MBRO}") (class "Default")
      (node (ref "CONTROL_LOGIC") (pin "4") (pinfunction "4_4") (pintype "bidirectional"))
      (node (ref "NOT_GATE_2") (pin "6") (pinfunction "3Y_6") (pintype "bidirectional"))
    )
    (net (code "67") (name "/~{MCR}") (class "Default")
      (node (ref "CONTROL_LOGIC") (pin "20") (pinfunction "20_20") (pintype "bidirectional"))
      (node (ref "MICROCODE_COUNTER") (pin "1") (pinfunction "~{CLR}_1") (pintype "bidirectional"))
      (node (ref "NOT_GATE_1") (pin "4") (pinfunction "2Y_4") (pintype "bidirectional"))
    )
    (net (code "68") (name "/~{ONE}") (class "Default")
      (node (ref "CONTROL_LOGIC") (pin "12") (pinfunction "12_12") (pintype "bidirectional"))
      (node (ref "NOT_GATE_1") (pin "2") (pinfunction "1Y_2") (pintype "bidirectional"))
      (node (ref "ONE_0-7") (pin "1") (pinfunction "~{OE1}_1") (pintype "bidirectional"))
      (node (ref "ONE_0-7") (pin "19") (pinfunction "~{OE2}_19") (pintype "bidirectional"))
      (node (ref "ONE_8-15") (pin "1") (pinfunction "~{OE1}_1") (pintype "bidirectional"))
      (node (ref "ONE_8-15") (pin "19") (pinfunction "~{OE2}_19") (pintype "bidirectional"))
    )
    (net (code "69") (name "/~{RI}") (class "Default")
      (node (ref "CONTROL_LOGIC") (pin "8") (pinfunction "8_8") (pintype "bidirectional"))
      (node (ref "NOT_GATE_2") (pin "12") (pinfunction "6Y_12") (pintype "bidirectional"))
    )
    (net (code "70") (name "/~{RO}") (class "Default")
      (node (ref "CONTROL_LOGIC") (pin "10") (pinfunction "10_10") (pintype "bidirectional"))
      (node (ref "NOT_GATE_2") (pin "10") (pinfunction "5Y_10") (pintype "bidirectional"))
    )
    (net (code "71") (name "/~{SC}") (class "Default")
      (node (ref "CONTROL_LOGIC") (pin "9") (pinfunction "9_9") (pintype "bidirectional"))
      (node (ref "NOT_GATE_1") (pin "6") (pinfunction "3Y_6") (pintype "bidirectional"))
    )
    (net (code "72") (name "Net-(CLOCK_GATE-1Y)") (class "Default")
      (node (ref "CLOCK_GATE") (pin "3") (pinfunction "1Y_3") (pintype "bidirectional"))
      (node (ref "IR_0-7") (pin "11") (pinfunction "CLK_11") (pintype "bidirectional"))
      (node (ref "IR_8-15") (pin "11") (pinfunction "CLK_11") (pintype "bidirectional"))
    )
    (net (code "73") (name "Net-(CONTROL_LOGIC_0-7-A0)") (class "Default")
      (node (ref "CONTROL_LOGIC_0-7") (pin "8") (pinfunction "A0_8") (pintype "bidirectional"))
      (node (ref "CONTROL_LOGIC_16-23") (pin "8") (pinfunction "A0_8") (pintype "bidirectional"))
      (node (ref "CONTROL_LOGIC_8-15") (pin "8") (pinfunction "A0_8") (pintype "bidirectional"))
      (node (ref "MICROCODE_COUNTER") (pin "14") (pinfunction "QA_14") (pintype "bidirectional"))
    )
    (net (code "74") (name "Net-(CONTROL_LOGIC_0-7-A1)") (class "Default")
      (node (ref "CONTROL_LOGIC_0-7") (pin "7") (pinfunction "A1_7") (pintype "bidirectional"))
      (node (ref "CONTROL_LOGIC_16-23") (pin "7") (pinfunction "A1_7") (pintype "bidirectional"))
      (node (ref "CONTROL_LOGIC_8-15") (pin "7") (pinfunction "A1_7") (pintype "bidirectional"))
      (node (ref "MICROCODE_COUNTER") (pin "13") (pinfunction "QB_13") (pintype "bidirectional"))
    )
    (net (code "75") (name "Net-(CONTROL_LOGIC_0-7-A2)") (class "Default")
      (node (ref "CONTROL_LOGIC_0-7") (pin "6") (pinfunction "A2_6") (pintype "bidirectional"))
      (node (ref "CONTROL_LOGIC_16-23") (pin "6") (pinfunction "A2_6") (pintype "bidirectional"))
      (node (ref "CONTROL_LOGIC_8-15") (pin "6") (pinfunction "A2_6") (pintype "bidirectional"))
      (node (ref "MICROCODE_COUNTER") (pin "12") (pinfunction "QC_12") (pintype "bidirectional"))
    )
    (net (code "76") (name "Net-(CONTROL_LOGIC_0-7-A3)") (class "Default")
      (node (ref "CONTROL_LOGIC_0-7") (pin "5") (pinfunction "A3_5") (pintype "bidirectional"))
      (node (ref "CONTROL_LOGIC_16-23") (pin "5") (pinfunction "A3_5") (pintype "bidirectional"))
      (node (ref "CONTROL_LOGIC_8-15") (pin "5") (pinfunction "A3_5") (pintype "bidirectional"))
      (node (ref "MICROCODE_COUNTER") (pin "11") (pinfunction "QD_11") (pintype "bidirectional"))
    )
    (net (code "77") (name "Net-(LED0-C)") (class "Default")
      (node (ref "LED0") (pin "K") (pinfunction "C_K") (pintype "passive"))
      (node (ref "LED1") (pin "K") (pinfunction "C_K") (pintype "passive"))
      (node (ref "LED10") (pin "K") (pinfunction "C_K") (pintype "passive"))
      (node (ref "LED11") (pin "K") (pinfunction "C_K") (pintype "passive"))
      (node (ref "LED12") (pin "K") (pinfunction "C_K") (pintype "passive"))
      (node (ref "LED13") (pin "K") (pinfunction "C_K") (pintype "passive"))
      (node (ref "LED14") (pin "K") (pinfunction "C_K") (pintype "passive"))
      (node (ref "LED15") (pin "K") (pinfunction "C_K") (pintype "passive"))
      (node (ref "LED2") (pin "K") (pinfunction "C_K") (pintype "passive"))
      (node (ref "LED3") (pin "K") (pinfunction "C_K") (pintype "passive"))
      (node (ref "LED4") (pin "K") (pinfunction "C_K") (pintype "passive"))
      (node (ref "LED5") (pin "K") (pinfunction "C_K") (pintype "passive"))
      (node (ref "LED6") (pin "K") (pinfunction "C_K") (pintype "passive"))
      (node (ref "LED7") (pin "K") (pinfunction "C_K") (pintype "passive"))
      (node (ref "LED8") (pin "K") (pinfunction "C_K") (pintype "passive"))
      (node (ref "LED9") (pin "K") (pinfunction "C_K") (pintype "passive"))
    )
    (net (code "78") (name "Net-(LED0-PadA)") (class "Default")
      (node (ref "LED0") (pin "A") (pinfunction "A_A") (pintype "passive"))
      (node (ref "R0") (pin "1") (pinfunction "1_1") (pintype "passive"))
    )
    (net (code "79") (name "Net-(LED1-PadA)") (class "Default")
      (node (ref "LED1") (pin "A") (pinfunction "A_A") (pintype "passive"))
      (node (ref "R1") (pin "1") (pinfunction "1_1") (pintype "passive"))
    )
    (net (code "80") (name "Net-(LED2-PadA)") (class "Default")
      (node (ref "LED2") (pin "A") (pinfunction "A_A") (pintype "passive"))
      (node (ref "R2") (pin "1") (pinfunction "1_1") (pintype "passive"))
    )
    (net (code "81") (name "Net-(LED3-PadA)") (class "Default")
      (node (ref "LED3") (pin "A") (pinfunction "A_A") (pintype "passive"))
      (node (ref "R3") (pin "1") (pinfunction "1_1") (pintype "passive"))
    )
    (net (code "82") (name "Net-(LED4-PadA)") (class "Default")
      (node (ref "LED4") (pin "A") (pinfunction "A_A") (pintype "passive"))
      (node (ref "R4") (pin "1") (pinfunction "1_1") (pintype "passive"))
    )
    (net (code "83") (name "Net-(LED5-PadA)") (class "Default")
      (node (ref "LED5") (pin "A") (pinfunction "A_A") (pintype "passive"))
      (node (ref "R5") (pin "1") (pinfunction "1_1") (pintype "passive"))
    )
    (net (code "84") (name "Net-(LED6-PadA)") (class "Default")
      (node (ref "LED6") (pin "A") (pinfunction "A_A") (pintype "passive"))
      (node (ref "R6") (pin "1") (pinfunction "1_1") (pintype "passive"))
    )
    (net (code "85") (name "Net-(LED7-PadA)") (class "Default")
      (node (ref "LED7") (pin "A") (pinfunction "A_A") (pintype "passive"))
      (node (ref "R7") (pin "1") (pinfunction "1_1") (pintype "passive"))
    )
    (net (code "86") (name "Net-(LED8-PadA)") (class "Default")
      (node (ref "LED8") (pin "A") (pinfunction "A_A") (pintype "passive"))
      (node (ref "R8") (pin "1") (pinfunction "1_1") (pintype "passive"))
    )
    (net (code "87") (name "Net-(LED9-PadA)") (class "Default")
      (node (ref "LED9") (pin "A") (pinfunction "A_A") (pintype "passive"))
      (node (ref "R9") (pin "1") (pinfunction "1_1") (pintype "passive"))
    )
    (net (code "88") (name "Net-(LED10-PadA)") (class "Default")
      (node (ref "LED10") (pin "A") (pinfunction "A_A") (pintype "passive"))
      (node (ref "R10") (pin "1") (pinfunction "1_1") (pintype "passive"))
    )
    (net (code "89") (name "Net-(LED11-PadA)") (class "Default")
      (node (ref "LED11") (pin "A") (pinfunction "A_A") (pintype "passive"))
      (node (ref "R11") (pin "1") (pinfunction "1_1") (pintype "passive"))
    )
    (net (code "90") (name "Net-(LED12-PadA)") (class "Default")
      (node (ref "LED12") (pin "A") (pinfunction "A_A") (pintype "passive"))
      (node (ref "R12") (pin "1") (pinfunction "1_1") (pintype "passive"))
    )
    (net (code "91") (name "Net-(LED13-PadA)") (class "Default")
      (node (ref "LED13") (pin "A") (pinfunction "A_A") (pintype "passive"))
      (node (ref "R13") (pin "1") (pinfunction "1_1") (pintype "passive"))
    )
    (net (code "92") (name "Net-(LED14-PadA)") (class "Default")
      (node (ref "LED14") (pin "A") (pinfunction "A_A") (pintype "passive"))
      (node (ref "R14") (pin "1") (pinfunction "1_1") (pintype "passive"))
    )
    (net (code "93") (name "Net-(LED15-PadA)") (class "Default")
      (node (ref "LED15") (pin "A") (pinfunction "A_A") (pintype "passive"))
      (node (ref "R15") (pin "1") (pinfunction "1_1") (pintype "passive"))
    )
    (net (code "94") (name "Net-(LEDACI-PadA)") (class "Default")
      (node (ref "LEDACI") (pin "A") (pinfunction "A_A") (pintype "passive"))
      (node (ref "RACI") (pin "1") (pinfunction "1_1") (pintype "passive"))
    )
    (net (code "95") (name "Net-(LEDACO-PadA)") (class "Default")
      (node (ref "LEDACO") (pin "A") (pinfunction "A_A") (pintype "passive"))
      (node (ref "RACO") (pin "1") (pinfunction "1_1") (pintype "passive"))
    )
    (net (code "96") (name "Net-(LEDALUO-PadA)") (class "Default")
      (node (ref "LEDALUO") (pin "A") (pinfunction "A_A") (pintype "passive"))
      (node (ref "RALUO") (pin "1") (pinfunction "1_1") (pintype "passive"))
    )
    (net (code "97") (name "Net-(LEDCE-PadA)") (class "Default")
      (node (ref "LEDCE") (pin "A") (pinfunction "A_A") (pintype "passive"))
      (node (ref "RCE") (pin "1") (pinfunction "1_1") (pintype "passive"))
    )
    (net (code "98") (name "Net-(LEDCO-PadA)") (class "Default")
      (node (ref "LEDCO") (pin "A") (pinfunction "A_A") (pintype "passive"))
      (node (ref "RCO") (pin "1") (pinfunction "1_1") (pintype "passive"))
    )
    (net (code "99") (name "Net-(LEDHLT-PadA)") (class "Default")
      (node (ref "LEDHLT") (pin "A") (pinfunction "A_A") (pintype "passive"))
      (node (ref "RHLT") (pin "1") (pinfunction "1_1") (pintype "passive"))
    )
    (net (code "100") (name "Net-(LEDINPUT-PadA)") (class "Default")
      (node (ref "LEDINPUT") (pin "A") (pinfunction "A_A") (pintype "passive"))
      (node (ref "RINPUT") (pin "1") (pinfunction "1_1") (pintype "passive"))
    )
    (net (code "101") (name "Net-(LEDIRI-PadA)") (class "Default")
      (node (ref "LEDIRI") (pin "A") (pinfunction "A_A") (pintype "passive"))
      (node (ref "RIRI") (pin "1") (pinfunction "1_1") (pintype "passive"))
    )
    (net (code "102") (name "Net-(LEDIRO-PadA)") (class "Default")
      (node (ref "LEDIRO") (pin "A") (pinfunction "A_A") (pintype "passive"))
      (node (ref "RIRO") (pin "1") (pinfunction "1_1") (pintype "passive"))
    )
    (net (code "103") (name "Net-(LEDJMP-PadA)") (class "Default")
      (node (ref "LEDJMP") (pin "A") (pinfunction "A_A") (pintype "passive"))
      (node (ref "RJMP") (pin "1") (pinfunction "1_1") (pintype "passive"))
    )
    (net (code "104") (name "Net-(LEDMARI-PadA)") (class "Default")
      (node (ref "LEDMARI") (pin "A") (pinfunction "A_A") (pintype "passive"))
      (node (ref "RMARI") (pin "1") (pinfunction "1_1") (pintype "passive"))
    )
    (net (code "105") (name "Net-(LEDMBRI-PadA)") (class "Default")
      (node (ref "LEDMBRI") (pin "A") (pinfunction "A_A") (pintype "passive"))
      (node (ref "RMBRI") (pin "1") (pinfunction "1_1") (pintype "passive"))
    )
    (net (code "106") (name "Net-(LEDMBRO-PadA)") (class "Default")
      (node (ref "LEDMBRO") (pin "A") (pinfunction "A_A") (pintype "passive"))
      (node (ref "RMBRO") (pin "1") (pinfunction "1_1") (pintype "passive"))
    )
    (net (code "107") (name "Net-(LEDMCR-PadA)") (class "Default")
      (node (ref "LEDMCR") (pin "A") (pinfunction "A_A") (pintype "passive"))
      (node (ref "RMCR") (pin "1") (pinfunction "1_1") (pintype "passive"))
    )
    (net (code "108") (name "Net-(LEDOI-PadA)") (class "Default")
      (node (ref "LEDOI") (pin "A") (pinfunction "A_A") (pintype "passive"))
      (node (ref "ROI") (pin "1") (pinfunction "1_1") (pintype "passive"))
    )
    (net (code "109") (name "Net-(LEDONE-PadA)") (class "Default")
      (node (ref "LEDONE") (pin "A") (pinfunction "A_A") (pintype "passive"))
      (node (ref "RONE") (pin "1") (pinfunction "1_1") (pintype "passive"))
    )
    (net (code "110") (name "Net-(LEDRI-PadA)") (class "Default")
      (node (ref "LEDRI") (pin "A") (pinfunction "A_A") (pintype "passive"))
      (node (ref "RRI") (pin "1") (pinfunction "1_1") (pintype "passive"))
    )
    (net (code "111") (name "Net-(LEDRO-PadA)") (class "Default")
      (node (ref "LEDRO") (pin "A") (pinfunction "A_A") (pintype "passive"))
      (node (ref "RRO") (pin "1") (pinfunction "1_1") (pintype "passive"))
    )
    (net (code "112") (name "Net-(LEDSC-PadA)") (class "Default")
      (node (ref "LEDSC") (pin "A") (pinfunction "A_A") (pintype "passive"))
      (node (ref "RSC") (pin "1") (pinfunction "1_1") (pintype "passive"))
    )
    (net (code "113") (name "Net-(LEDSU-PadA)") (class "Default")
      (node (ref "LEDSU") (pin "A") (pinfunction "A_A") (pintype "passive"))
      (node (ref "RSU") (pin "1") (pinfunction "1_1") (pintype "passive"))
    )
    (net (code "114") (name "unconnected-(CLOCK_GATE-2Y-Pad6)") (class "Default")
      (node (ref "CLOCK_GATE") (pin "6") (pinfunction "2Y_6") (pintype "bidirectional"))
    )
    (net (code "115") (name "unconnected-(CLOCK_GATE-3Y-Pad8)") (class "Default")
      (node (ref "CLOCK_GATE") (pin "8") (pinfunction "3Y_8") (pintype "bidirectional"))
    )
    (net (code "116") (name "unconnected-(CLOCK_GATE-4Y-Pad11)") (class "Default")
      (node (ref "CLOCK_GATE") (pin "11") (pinfunction "4Y_11") (pintype "bidirectional"))
    )
    (net (code "117") (name "unconnected-(MICROCODE_COUNTER-RCO-Pad15)") (class "Default")
      (node (ref "MICROCODE_COUNTER") (pin "15") (pinfunction "RCO_15") (pintype "bidirectional"))
    )
    (net (code "118") (name "unconnected-(NOT_GATE_2-1Y-Pad2)") (class "Default")
      (node (ref "NOT_GATE_2") (pin "2") (pinfunction "1Y_2") (pintype "bidirectional"))
    )
  )
)
